# BabyBoy.net
KiCad netlist of a schematic drawn in EAGLE
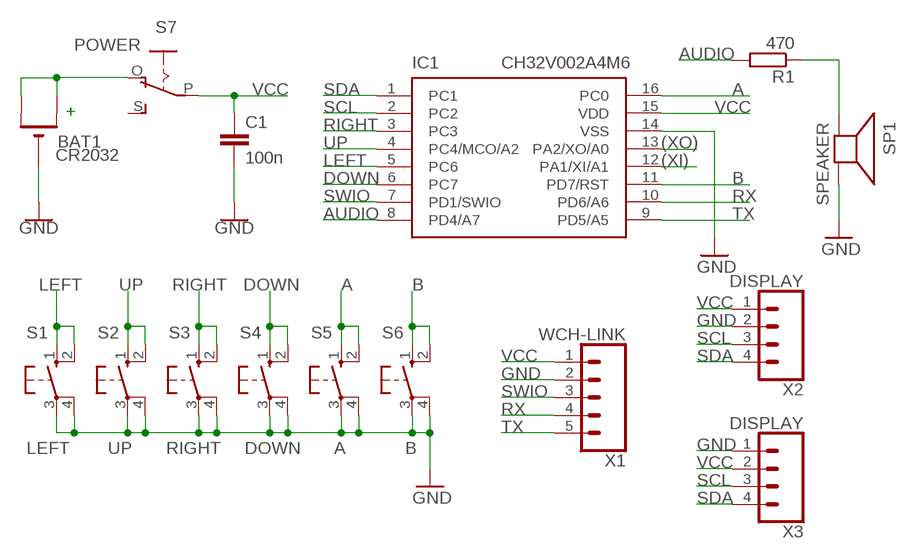
[diagram p0: schematic, sheet 1]

(export (version "E")
  (design (tool "Eeschema 10.0.6"))
  (components
    (comp (ref "BAT1")
      (value "CR2032")
      (footprint "eagle-import:CR2032-THRU")
      (libsource (lib "eagle-import") (part "CR2032THM"))
    )
    (comp (ref "C1")
      (value "100n")
      (footprint "eagle-import:C050-024X044")
      (libsource (lib "eagle-import") (part "C-EU050-024X044"))
    )
    (comp (ref "IC1")
      (value "CH32V002A4M6")
      (footprint "eagle-import:SOP16")
      (libsource (lib "eagle-import") (part "CH32V002A4M6"))
    )
    (comp (ref "R1")
      (value "470")
      (footprint "eagle-import:0204_7")
      (libsource (lib "eagle-import") (part "R-EU_0204/7"))
    )
    (comp (ref "S1")
      (value "LEFT")
      (footprint "eagle-import:B3F-10XX")
      (fields (field (name "MPN") "B3F-1000"))
      (libsource (lib "eagle-import") (part "10-XX"))
    )
    (comp (ref "S2")
      (value "UP")
      (footprint "eagle-import:B3F-10XX")
      (fields (field (name "MPN") "B3F-1000"))
      (libsource (lib "eagle-import") (part "10-XX"))
    )
    (comp (ref "S3")
      (value "RIGHT")
      (footprint "eagle-import:B3F-10XX")
      (fields (field (name "MPN") "B3F-1000"))
      (libsource (lib "eagle-import") (part "10-XX"))
    )
    (comp (ref "S4")
      (value "DOWN")
      (footprint "eagle-import:B3F-10XX")
      (fields (field (name "MPN") "B3F-1000"))
      (libsource (lib "eagle-import") (part "10-XX"))
    )
    (comp (ref "S5")
      (value "A")
      (footprint "eagle-import:B3F-10XX")
      (fields (field (name "MPN") "B3F-1000"))
      (libsource (lib "eagle-import") (part "10-XX"))
    )
    (comp (ref "S6")
      (value "B")
      (footprint "eagle-import:B3F-10XX")
      (fields (field (name "MPN") "B3F-1000"))
      (libsource (lib "eagle-import") (part "10-XX"))
    )
    (comp (ref "S7")
      (value "POWER")
      (footprint "eagle-import:EG1218")
      (libsource (lib "eagle-import") (part "EG1218S"))
    )
    (comp (ref "SP1")
      (value "SPEAKER")
      (footprint "eagle-import:AL60P")
      (libsource (lib "eagle-import") (part "SPEAKER/AL60P"))
    )
    (comp (ref "X1")
      (value "WCH-LINK")
      (footprint "eagle-import:1X05_LONGPADS")
      (libsource (lib "eagle-import") (part "CONN_05PTH_LONGPADS"))
    )
    (comp (ref "X2")
      (value "DISPLAY")
      (footprint "eagle-import:1X04")
      (libsource (lib "eagle-import") (part "CONN_04"))
    )
    (comp (ref "X3")
      (value "DISPLAY")
      (footprint "eagle-import:1X04")
      (libsource (lib "eagle-import") (part "CONN_04"))
    )
  )
  (nets
    (net (code "1") (name "/(XI)") (class "Default")
      (node (ref "IC1") (pin "12") (pinfunction "PA1/XI/A1_12") (pintype "bidirectional"))
    )
    (net (code "2") (name "/(XO)") (class "Default")
      (node (ref "IC1") (pin "13") (pinfunction "PA2/XO/A0_13") (pintype "bidirectional"))
    )
    (net (code "3") (name "/A") (class "Default")
      (node (ref "IC1") (pin "16") (pinfunction "PC0_16") (pintype "bidirectional"))
      (node (ref "S5") (pin "1") (pinfunction "S_1") (pintype "passive"))
      (node (ref "S5") (pin "2") (pinfunction "S1_2") (pintype "passive"))
    )
    (net (code "4") (name "/AUDIO") (class "Default")
      (node (ref "IC1") (pin "8") (pinfunction "PD4/A7_8") (pintype "bidirectional"))
      (node (ref "R1") (pin "2") (pinfunction "2_2") (pintype "passive"))
    )
    (net (code "5") (name "/B") (class "Default")
      (node (ref "IC1") (pin "11") (pinfunction "PD7/RST_11") (pintype "bidirectional"))
      (node (ref "S6") (pin "1") (pinfunction "S_1") (pintype "passive"))
      (node (ref "S6") (pin "2") (pinfunction "S1_2") (pintype "passive"))
    )
    (net (code "6") (name "/DOWN") (class "Default")
      (node (ref "IC1") (pin "6") (pinfunction "PC7_6") (pintype "bidirectional"))
      (node (ref "S4") (pin "1") (pinfunction "S_1") (pintype "passive"))
      (node (ref "S4") (pin "2") (pinfunction "S1_2") (pintype "passive"))
    )
    (net (code "7") (name "/LEFT") (class "Default")
      (node (ref "IC1") (pin "5") (pinfunction "PC6_5") (pintype "bidirectional"))
      (node (ref "S1") (pin "1") (pinfunction "S_1") (pintype "passive"))
      (node (ref "S1") (pin "2") (pinfunction "S1_2") (pintype "passive"))
    )
    (net (code "8") (name "/RIGHT") (class "Default")
      (node (ref "IC1") (pin "3") (pinfunction "PC3_3") (pintype "bidirectional"))
      (node (ref "S3") (pin "1") (pinfunction "S_1") (pintype "passive"))
      (node (ref "S3") (pin "2") (pinfunction "S1_2") (pintype "passive"))
    )
    (net (code "9") (name "/RX") (class "Default")
      (node (ref "IC1") (pin "10") (pinfunction "PD6/A6_10") (pintype "bidirectional"))
      (node (ref "X1") (pin "4") (pinfunction "4_4") (pintype "passive"))
    )
    (net (code "10") (name "/SCL") (class "Default")
      (node (ref "IC1") (pin "2") (pinfunction "PC2_2") (pintype "bidirectional"))
      (node (ref "X2") (pin "3") (pinfunction "3_3") (pintype "passive"))
      (node (ref "X3") (pin "3") (pinfunction "3_3") (pintype "passive"))
    )
    (net (code "11") (name "/SDA") (class "Default")
      (node (ref "IC1") (pin "1") (pinfunction "PC1_1") (pintype "bidirectional"))
      (node (ref "X2") (pin "4") (pinfunction "4_4") (pintype "passive"))
      (node (ref "X3") (pin "4") (pinfunction "4_4") (pintype "passive"))
    )
    (net (code "12") (name "/SWIO") (class "Default")
      (node (ref "IC1") (pin "7") (pinfunction "PD1/SWIO_7") (pintype "bidirectional"))
      (node (ref "X1") (pin "3") (pinfunction "3_3") (pintype "passive"))
    )
    (net (code "13") (name "/TX") (class "Default")
      (node (ref "IC1") (pin "9") (pinfunction "PD5/A5_9") (pintype "bidirectional"))
      (node (ref "X1") (pin "5") (pinfunction "5_5") (pintype "passive"))
    )
    (net (code "14") (name "/UP") (class "Default")
      (node (ref "IC1") (pin "4") (pinfunction "PC4/MCO/A2_4") (pintype "bidirectional"))
      (node (ref "S2") (pin "1") (pinfunction "S_1") (pintype "passive"))
      (node (ref "S2") (pin "2") (pinfunction "S1_2") (pintype "passive"))
    )
    (net (code "15") (name "/VCC") (class "Default")
      (node (ref "C1") (pin "1") (pinfunction "1_1") (pintype "passive"))
      (node (ref "IC1") (pin "15") (pinfunction "VDD_15") (pintype "power_in"))
      (node (ref "S7") (pin "P") (pinfunction "P_P") (pintype "passive"))
      (node (ref "X1") (pin "1") (pinfunction "1_1") (pintype "passive"))
      (node (ref "X2") (pin "1") (pinfunction "1_1") (pintype "passive"))
      (node (ref "X3") (pin "2") (pinfunction "2_2") (pintype "passive"))
    )
    (net (code "16") (name "GND") (class "Default")
      (node (ref "BAT1") (pin "-") (pinfunction "-_-") (pintype "passive"))
      (node (ref "C1") (pin "2") (pinfunction "2_2") (pintype "passive"))
      (node (ref "IC1") (pin "14") (pinfunction "VSS_14") (pintype "power_in"))
      (node (ref "S1") (pin "3") (pinfunction "P_3") (pintype "passive"))
      (node (ref "S1") (pin "4") (pinfunction "P1_4") (pintype "passive"))
      (node (ref "S2") (pin "3") (pinfunction "P_3") (pintype "passive"))
      (node (ref "S2") (pin "4") (pinfunction "P1_4") (pintype "passive"))
      (node (ref "S3") (pin "3") (pinfunction "P_3") (pintype "passive"))
      (node (ref "S3") (pin "4") (pinfunction "P1_4") (pintype "passive"))
      (node (ref "S4") (pin "3") (pinfunction "P_3") (pintype "passive"))
      (node (ref "S4") (pin "4") (pinfunction "P1_4") (pintype "passive"))
      (node (ref "S5") (pin "3") (pinfunction "P_3") (pintype "passive"))
      (node (ref "S5") (pin "4") (pinfunction "P1_4") (pintype "passive"))
      (node (ref "S6") (pin "3") (pinfunction "P_3") (pintype "passive"))
      (node (ref "S6") (pin "4") (pinfunction "P1_4") (pintype "passive"))
      (node (ref "SP1") (pin "2") (pinfunction "-_2") (pintype "passive"))
      (node (ref "X1") (pin "2") (pinfunction "2_2") (pintype "passive"))
      (node (ref "X2") (pin "2") (pinfunction "2_2") (pintype "passive"))
      (node (ref "X3") (pin "1") (pinfunction "1_1") (pintype "passive"))
    )
    (net (code "17") (name "Net-(BAT1-+)") (class "Default")
      (node (ref "BAT1") (pin "+1") (pinfunction "+_+1") (pintype "passive"))
      (node (ref "BAT1") (pin "+2") (pinfunction "+1_+2") (pintype "passive"))
      (node (ref "S7") (pin "O") (pinfunction "O_O") (pintype "passive"))
    )
    (net (code "18") (name "Net-(SP1-+)") (class "Default")
      (node (ref "R1") (pin "1") (pinfunction "1_1") (pintype "passive"))
      (node (ref "SP1") (pin "1") (pinfunction "+_1") (pintype "passive"))
    )
    (net (code "19") (name "unconnected-(S7-PadS)") (class "Default")
      (node (ref "S7") (pin "S") (pinfunction "S_S") (pintype "passive"))
    )
  )
)
